# SH2_-_CONNECTORS_1.net
KiCad netlist of a schematic drawn in Altium Designer
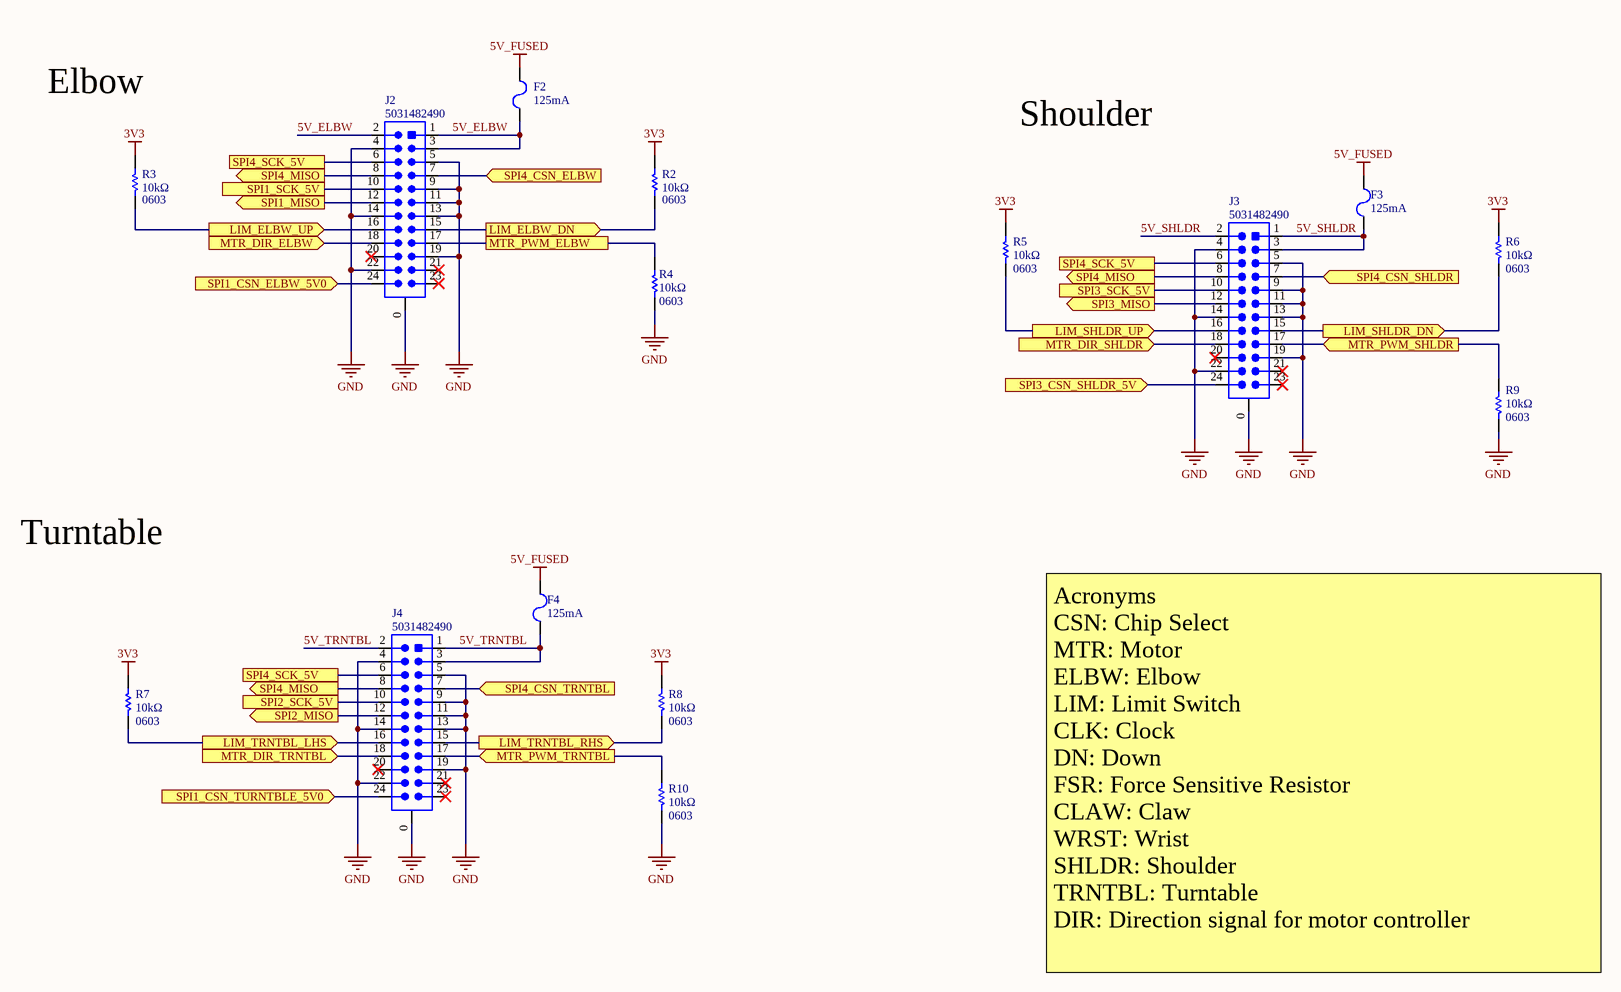
[diagram p0: SH2 - CONNECTORS_1.SchDoc]

(export (version "E")
  (design (tool "Eeschema 10.0.6"))
  (components
    (comp (ref "F2")
      (value "FUSE_125mA_1206")
      (footprint "FUSE_1206")
      (description "FUSE BOARD MNT 125MA 125VAC/VDC")
      (fields (field (name "CURRENT RATING") "125mA"))
      (libsource (lib "UWRT_Schematic_Library_2020") (part "FUSE_125mA_1206"))
    )
    (comp (ref "F3")
      (value "FUSE_125mA_1206")
      (footprint "FUSE_1206")
      (description "FUSE BOARD MNT 125MA 125VAC/VDC")
      (fields (field (name "CURRENT RATING") "125mA"))
      (libsource (lib "UWRT_Schematic_Library_2020") (part "FUSE_125mA_1206"))
    )
    (comp (ref "F4")
      (value "FUSE_125mA_1206")
      (footprint "FUSE_1206")
      (description "FUSE BOARD MNT 125MA 125VAC/VDC")
      (fields (field (name "CURRENT RATING") "125mA"))
      (libsource (lib "UWRT_Schematic_Library_2020") (part "FUSE_125mA_1206"))
    )
    (comp (ref "J2")
      (value "CON_12x2M_SM_RA")
      (footprint "MOLEX-5031482490")
      (description "CONN HEADER SMD RIGHT ANGLE 1.5MM PITCH")
      (fields (field (name "MANUFACTURER PART NUMBER 1") "5031482490"))
      (libsource (lib "UWRT_Schematic_Library_2020") (part "CON_12x2M_SM_RA"))
    )
    (comp (ref "J3")
      (value "CON_12x2M_SM_RA")
      (footprint "MOLEX-5031482490")
      (description "CONN HEADER SMD RIGHT ANGLE 1.5MM PITCH")
      (fields (field (name "MANUFACTURER PART NUMBER 1") "5031482490"))
      (libsource (lib "UWRT_Schematic_Library_2020") (part "CON_12x2M_SM_RA"))
    )
    (comp (ref "J4")
      (value "CON_12x2M_SM_RA")
      (footprint "MOLEX-5031482490")
      (description "CONN HEADER SMD RIGHT ANGLE 1.5MM PITCH")
      (fields (field (name "MANUFACTURER PART NUMBER 1") "5031482490"))
      (libsource (lib "UWRT_Schematic_Library_2020") (part "CON_12x2M_SM_RA"))
    )
    (comp (ref "R2")
      (value "10kΩ")
      (footprint "RESC0603")
      (description "RES 10K OHM 5% 1/10W 0603")
      (fields (field (name "PACKAGE/FOOTPRINT") "0603") (field (name "Comment") "RES_10kΩ_0603_5%"))
      (libsource (lib "UWRT_Schematic_Library_2020") (part "RES_10kΩ_0603_5%"))
    )
    (comp (ref "R3")
      (value "10kΩ")
      (footprint "RESC0603")
      (description "RES 10K OHM 5% 1/10W 0603")
      (fields (field (name "PACKAGE/FOOTPRINT") "0603") (field (name "Comment") "RES_10kΩ_0603_5%"))
      (libsource (lib "UWRT_Schematic_Library_2020") (part "RES_10kΩ_0603_5%"))
    )
    (comp (ref "R4")
      (value "10kΩ")
      (footprint "RESC0603")
      (description "RES 10K OHM 5% 1/10W 0603")
      (fields (field (name "PACKAGE/FOOTPRINT") "0603") (field (name "Comment") "RES_10kΩ_0603_5%"))
      (libsource (lib "UWRT_Schematic_Library_2020") (part "RES_10kΩ_0603_5%"))
    )
    (comp (ref "R5")
      (value "10kΩ")
      (footprint "RESC0603")
      (description "RES 10K OHM 5% 1/10W 0603")
      (fields (field (name "PACKAGE/FOOTPRINT") "0603") (field (name "Comment") "RES_10kΩ_0603_5%"))
      (libsource (lib "UWRT_Schematic_Library_2020") (part "RES_10kΩ_0603_5%"))
    )
    (comp (ref "R6")
      (value "10kΩ")
      (footprint "RESC0603")
      (description "RES 10K OHM 5% 1/10W 0603")
      (fields (field (name "PACKAGE/FOOTPRINT") "0603") (field (name "Comment") "RES_10kΩ_0603_5%"))
      (libsource (lib "UWRT_Schematic_Library_2020") (part "RES_10kΩ_0603_5%"))
    )
    (comp (ref "R7")
      (value "10kΩ")
      (footprint "RESC0603")
      (description "RES 10K OHM 5% 1/10W 0603")
      (fields (field (name "PACKAGE/FOOTPRINT") "0603") (field (name "Comment") "RES_10kΩ_0603_5%"))
      (libsource (lib "UWRT_Schematic_Library_2020") (part "RES_10kΩ_0603_5%"))
    )
    (comp (ref "R8")
      (value "10kΩ")
      (footprint "RESC0603")
      (description "RES 10K OHM 5% 1/10W 0603")
      (fields (field (name "PACKAGE/FOOTPRINT") "0603") (field (name "Comment") "RES_10kΩ_0603_5%"))
      (libsource (lib "UWRT_Schematic_Library_2020") (part "RES_10kΩ_0603_5%"))
    )
    (comp (ref "R9")
      (value "10kΩ")
      (footprint "RESC0603")
      (description "RES 10K OHM 5% 1/10W 0603")
      (fields (field (name "PACKAGE/FOOTPRINT") "0603") (field (name "Comment") "RES_10kΩ_0603_5%"))
      (libsource (lib "UWRT_Schematic_Library_2020") (part "RES_10kΩ_0603_5%"))
    )
    (comp (ref "R10")
      (value "10kΩ")
      (footprint "RESC0603")
      (description "RES 10K OHM 5% 1/10W 0603")
      (fields (field (name "PACKAGE/FOOTPRINT") "0603") (field (name "Comment") "RES_10kΩ_0603_5%"))
      (libsource (lib "UWRT_Schematic_Library_2020") (part "RES_10kΩ_0603_5%"))
    )
  )
  (nets
    (net (code "1") (name "/5V_ELBW") (class "Default")
      (node (ref "F2") (pin "1") (pinfunction "1_1") (pintype "passive"))
      (node (ref "J2") (pin "1") (pinfunction "1_1") (pintype "passive"))
      (node (ref "J2") (pin "2") (pinfunction "2_2") (pintype "passive"))
      (node (ref "J2") (pin "3") (pinfunction "3_3") (pintype "passive"))
    )
    (net (code "2") (name "/5V_SHLDR") (class "Default")
      (node (ref "F3") (pin "1") (pinfunction "1_1") (pintype "passive"))
      (node (ref "J3") (pin "1") (pinfunction "1_1") (pintype "passive"))
      (node (ref "J3") (pin "2") (pinfunction "2_2") (pintype "passive"))
      (node (ref "J3") (pin "3") (pinfunction "3_3") (pintype "passive"))
    )
    (net (code "3") (name "/5V_TRNTBL") (class "Default")
      (node (ref "F4") (pin "1") (pinfunction "1_1") (pintype "passive"))
      (node (ref "J4") (pin "1") (pinfunction "1_1") (pintype "passive"))
      (node (ref "J4") (pin "2") (pinfunction "2_2") (pintype "passive"))
      (node (ref "J4") (pin "3") (pinfunction "3_3") (pintype "passive"))
    )
    (net (code "4") (name "/LIM_ELBW_DN") (class "Default")
      (node (ref "J2") (pin "15") (pinfunction "15_15") (pintype "passive"))
      (node (ref "R2") (pin "1") (pinfunction "1_1") (pintype "passive"))
    )
    (net (code "5") (name "/LIM_ELBW_UP") (class "Default")
      (node (ref "J2") (pin "16") (pinfunction "16_16") (pintype "passive"))
      (node (ref "R3") (pin "1") (pinfunction "1_1") (pintype "passive"))
    )
    (net (code "6") (name "/LIM_SHLDR_DN") (class "Default")
      (node (ref "J3") (pin "15") (pinfunction "15_15") (pintype "passive"))
      (node (ref "R6") (pin "1") (pinfunction "1_1") (pintype "passive"))
    )
    (net (code "7") (name "/LIM_SHLDR_UP") (class "Default")
      (node (ref "J3") (pin "16") (pinfunction "16_16") (pintype "passive"))
      (node (ref "R5") (pin "1") (pinfunction "1_1") (pintype "passive"))
    )
    (net (code "8") (name "/LIM_TRNTBL_LHS") (class "Default")
      (node (ref "J4") (pin "16") (pinfunction "16_16") (pintype "passive"))
      (node (ref "R7") (pin "1") (pinfunction "1_1") (pintype "passive"))
    )
    (net (code "9") (name "/LIM_TRNTBL_RHS") (class "Default")
      (node (ref "J4") (pin "15") (pinfunction "15_15") (pintype "passive"))
      (node (ref "R8") (pin "1") (pinfunction "1_1") (pintype "passive"))
    )
    (net (code "10") (name "/MTR_DIR_ELBW") (class "Default")
      (node (ref "J2") (pin "18") (pinfunction "18_18") (pintype "passive"))
    )
    (net (code "11") (name "/MTR_DIR_SHLDR") (class "Default")
      (node (ref "J3") (pin "18") (pinfunction "18_18") (pintype "passive"))
    )
    (net (code "12") (name "/MTR_DIR_TRNTBL") (class "Default")
      (node (ref "J4") (pin "18") (pinfunction "18_18") (pintype "passive"))
    )
    (net (code "13") (name "/MTR_PWM_ELBW") (class "Default")
      (node (ref "J2") (pin "17") (pinfunction "17_17") (pintype "passive"))
      (node (ref "R4") (pin "2") (pinfunction "2_2") (pintype "passive"))
    )
    (net (code "14") (name "/MTR_PWM_SHLDR") (class "Default")
      (node (ref "J3") (pin "17") (pinfunction "17_17") (pintype "passive"))
      (node (ref "R9") (pin "2") (pinfunction "2_2") (pintype "passive"))
    )
    (net (code "15") (name "/MTR_PWM_TRNTBL") (class "Default")
      (node (ref "J4") (pin "17") (pinfunction "17_17") (pintype "passive"))
      (node (ref "R10") (pin "2") (pinfunction "2_2") (pintype "passive"))
    )
    (net (code "16") (name "/SPI1_CSN_ELBW_5V0") (class "Default")
      (node (ref "J2") (pin "24") (pinfunction "24_24") (pintype "passive"))
    )
    (net (code "17") (name "/SPI1_CSN_TURNTBLE_5V0") (class "Default")
      (node (ref "J4") (pin "24") (pinfunction "24_24") (pintype "passive"))
    )
    (net (code "18") (name "/SPI1_MISO") (class "Default")
      (node (ref "J2") (pin "12") (pinfunction "12_12") (pintype "passive"))
    )
    (net (code "19") (name "/SPI1_SCK_5V") (class "Default")
      (node (ref "J2") (pin "10") (pinfunction "10_10") (pintype "passive"))
    )
    (net (code "20") (name "/SPI2_MISO") (class "Default")
      (node (ref "J4") (pin "12") (pinfunction "12_12") (pintype "passive"))
    )
    (net (code "21") (name "/SPI2_SCK_5V") (class "Default")
      (node (ref "J4") (pin "10") (pinfunction "10_10") (pintype "passive"))
    )
    (net (code "22") (name "/SPI3_CSN_SHLDR_5V") (class "Default")
      (node (ref "J3") (pin "24") (pinfunction "24_24") (pintype "passive"))
    )
    (net (code "23") (name "/SPI3_MISO") (class "Default")
      (node (ref "J3") (pin "12") (pinfunction "12_12") (pintype "passive"))
    )
    (net (code "24") (name "/SPI3_SCK_5V") (class "Default")
      (node (ref "J3") (pin "10") (pinfunction "10_10") (pintype "passive"))
    )
    (net (code "25") (name "/SPI4_CSN_ELBW") (class "Default")
      (node (ref "J2") (pin "7") (pinfunction "7_7") (pintype "passive"))
    )
    (net (code "26") (name "/SPI4_CSN_SHLDR") (class "Default")
      (node (ref "J3") (pin "7") (pinfunction "7_7") (pintype "passive"))
    )
    (net (code "27") (name "/SPI4_CSN_TRNTBL") (class "Default")
      (node (ref "J4") (pin "7") (pinfunction "7_7") (pintype "passive"))
    )
    (net (code "28") (name "/SPI4_MISO") (class "Default")
      (node (ref "J2") (pin "8") (pinfunction "8_8") (pintype "passive"))
      (node (ref "J3") (pin "8") (pinfunction "8_8") (pintype "passive"))
      (node (ref "J4") (pin "8") (pinfunction "8_8") (pintype "passive"))
    )
    (net (code "29") (name "/SPI4_SCK_5V") (class "Default")
      (node (ref "J2") (pin "6") (pinfunction "6_6") (pintype "passive"))
      (node (ref "J3") (pin "6") (pinfunction "6_6") (pintype "passive"))
      (node (ref "J4") (pin "6") (pinfunction "6_6") (pintype "passive"))
    )
    (net (code "30") (name "3V3") (class "Default")
      (node (ref "R2") (pin "2") (pinfunction "2_2") (pintype "passive"))
      (node (ref "R3") (pin "2") (pinfunction "2_2") (pintype "passive"))
      (node (ref "R5") (pin "2") (pinfunction "2_2") (pintype "passive"))
      (node (ref "R6") (pin "2") (pinfunction "2_2") (pintype "passive"))
      (node (ref "R7") (pin "2") (pinfunction "2_2") (pintype "passive"))
      (node (ref "R8") (pin "2") (pinfunction "2_2") (pintype "passive"))
    )
    (net (code "31") (name "5V_FUSED") (class "Default")
      (node (ref "F2") (pin "2") (pinfunction "2_2") (pintype "passive"))
      (node (ref "F3") (pin "2") (pinfunction "2_2") (pintype "passive"))
      (node (ref "F4") (pin "2") (pinfunction "2_2") (pintype "passive"))
    )
    (net (code "32") (name "GND") (class "Default")
      (node (ref "J2") (pin "0") (pinfunction "0_0") (pintype "passive"))
      (node (ref "J2") (pin "11") (pinfunction "11_11") (pintype "passive"))
      (node (ref "J2") (pin "13") (pinfunction "13_13") (pintype "passive"))
      (node (ref "J2") (pin "14") (pinfunction "14_14") (pintype "passive"))
      (node (ref "J2") (pin "19") (pinfunction "19_19") (pintype "passive"))
      (node (ref "J2") (pin "22") (pinfunction "22_22") (pintype "passive"))
      (node (ref "J2") (pin "4") (pinfunction "4_4") (pintype "passive"))
      (node (ref "J2") (pin "5") (pinfunction "5_5") (pintype "passive"))
      (node (ref "J2") (pin "9") (pinfunction "9_9") (pintype "passive"))
      (node (ref "J3") (pin "0") (pinfunction "0_0") (pintype "passive"))
      (node (ref "J3") (pin "11") (pinfunction "11_11") (pintype "passive"))
      (node (ref "J3") (pin "13") (pinfunction "13_13") (pintype "passive"))
      (node (ref "J3") (pin "14") (pinfunction "14_14") (pintype "passive"))
      (node (ref "J3") (pin "19") (pinfunction "19_19") (pintype "passive"))
      (node (ref "J3") (pin "22") (pinfunction "22_22") (pintype "passive"))
      (node (ref "J3") (pin "4") (pinfunction "4_4") (pintype "passive"))
      (node (ref "J3") (pin "5") (pinfunction "5_5") (pintype "passive"))
      (node (ref "J3") (pin "9") (pinfunction "9_9") (pintype "passive"))
      (node (ref "J4") (pin "0") (pinfunction "0_0") (pintype "passive"))
      (node (ref "J4") (pin "11") (pinfunction "11_11") (pintype "passive"))
      (node (ref "J4") (pin "13") (pinfunction "13_13") (pintype "passive"))
      (node (ref "J4") (pin "14") (pinfunction "14_14") (pintype "passive"))
      (node (ref "J4") (pin "19") (pinfunction "19_19") (pintype "passive"))
      (node (ref "J4") (pin "22") (pinfunction "22_22") (pintype "passive"))
      (node (ref "J4") (pin "4") (pinfunction "4_4") (pintype "passive"))
      (node (ref "J4") (pin "5") (pinfunction "5_5") (pintype "passive"))
      (node (ref "J4") (pin "9") (pinfunction "9_9") (pintype "passive"))
      (node (ref "R10") (pin "1") (pinfunction "1_1") (pintype "passive"))
      (node (ref "R4") (pin "1") (pinfunction "1_1") (pintype "passive"))
      (node (ref "R9") (pin "1") (pinfunction "1_1") (pintype "passive"))
    )
    (net (code "33") (name "unconnected-(J2-Pad20)") (class "Default")
      (node (ref "J2") (pin "20") (pinfunction "20_20") (pintype "passive+no_connect"))
    )
    (net (code "34") (name "unconnected-(J2-Pad21)") (class "Default")
      (node (ref "J2") (pin "21") (pinfunction "21_21") (pintype "passive+no_connect"))
    )
    (net (code "35") (name "unconnected-(J2-Pad23)") (class "Default")
      (node (ref "J2") (pin "23") (pinfunction "23_23") (pintype "passive+no_connect"))
    )
    (net (code "36") (name "unconnected-(J3-Pad20)") (class "Default")
      (node (ref "J3") (pin "20") (pinfunction "20_20") (pintype "passive+no_connect"))
    )
    (net (code "37") (name "unconnected-(J3-Pad21)") (class "Default")
      (node (ref "J3") (pin "21") (pinfunction "21_21") (pintype "passive+no_connect"))
    )
    (net (code "38") (name "unconnected-(J3-Pad23)") (class "Default")
      (node (ref "J3") (pin "23") (pinfunction "23_23") (pintype "passive+no_connect"))
    )
    (net (code "39") (name "unconnected-(J4-Pad20)") (class "Default")
      (node (ref "J4") (pin "20") (pinfunction "20_20") (pintype "passive+no_connect"))
    )
    (net (code "40") (name "unconnected-(J4-Pad21)") (class "Default")
      (node (ref "J4") (pin "21") (pinfunction "21_21") (pintype "passive+no_connect"))
    )
    (net (code "41") (name "unconnected-(J4-Pad23)") (class "Default")
      (node (ref "J4") (pin "23") (pinfunction "23_23") (pintype "passive+no_connect"))
    )
  )
)
